# 03_Schematic.net
KiCad netlist of a schematic drawn in Altium Designer
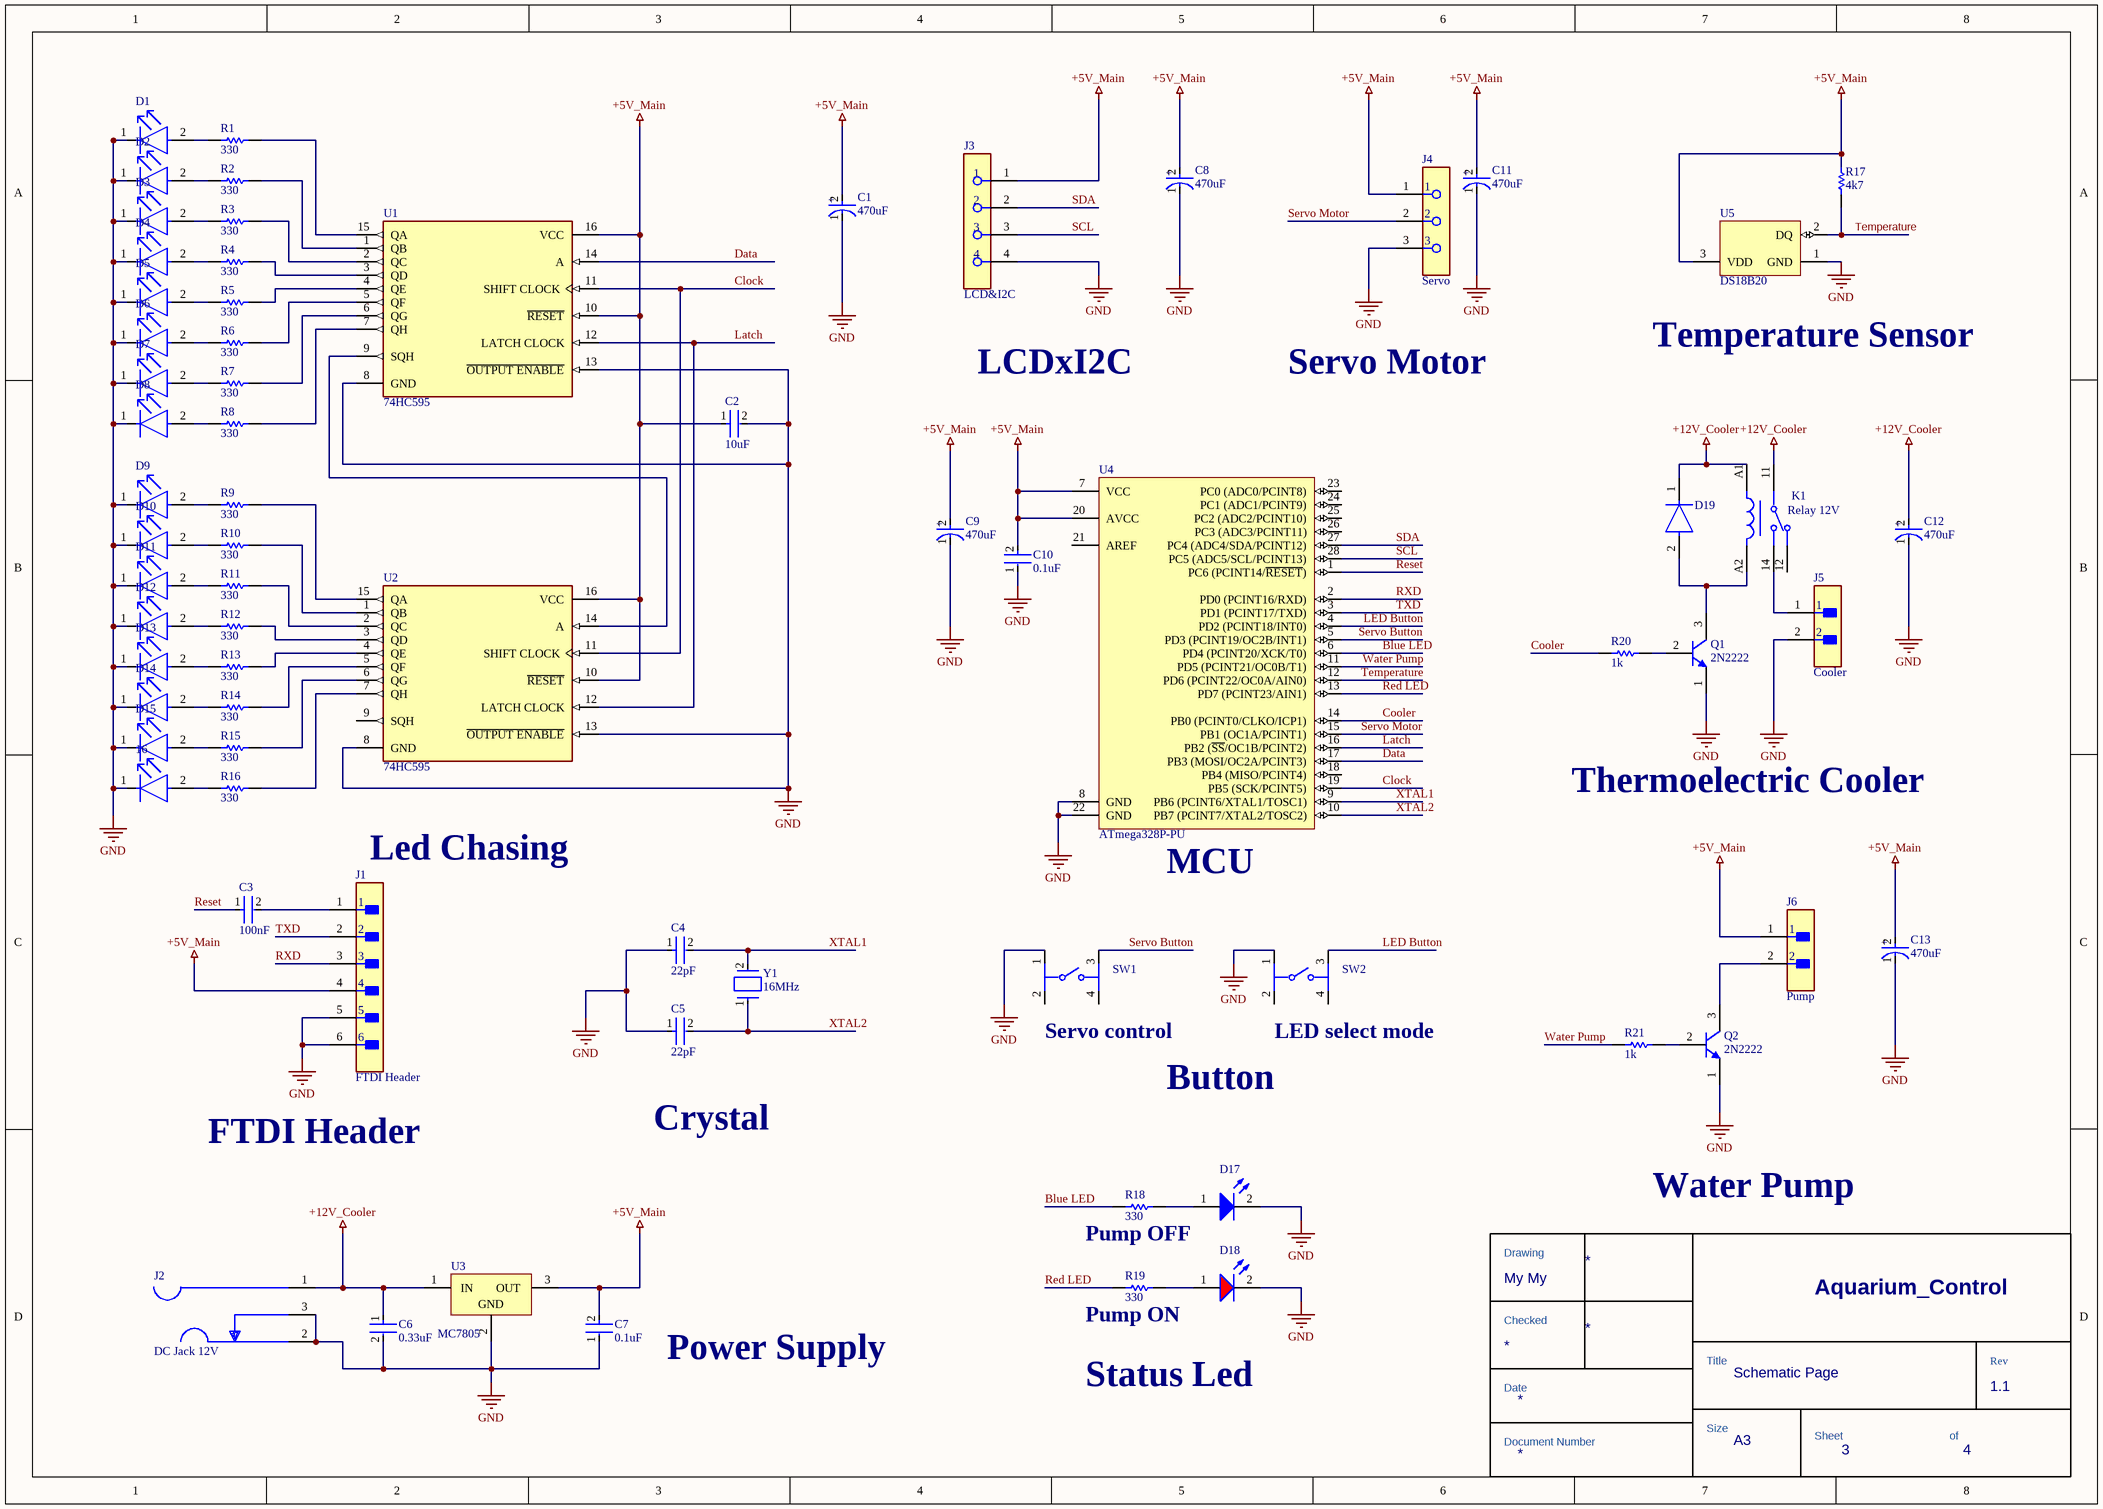
[diagram p0: 03.Schematic.SchDoc]

(export (version "E")
  (design (tool "Eeschema 10.0.6"))
  (components
    (comp (ref "16")
      (value "HLMP-1719")
      (footprint "FP-HLMP-1719-MFG")
      (description "LED YELLOW DIFFUSED T-1 T/H")
      (fields
        (field (name "MANUFACTURER") "Broadcom")
        (field (name "OCTOPART") "https://octopart.com/hlmp-1719-broadcom-71130405")
      )
      (libsource (lib "Altium Content Vault") (part "8706943c75ba83719d021d2fdc84c58"))
    )
    (comp (ref "C1")
      (value "470uF")
      (footprint "FP-FTF-MFG")
      (description "CAP ALUM 470UF 20% 25V SMD")
      (fields (field (name "VOLTAGE") "25V") (field (name "TOLERANCE") "20%"))
      (libsource (lib "Altium Content Vault") (part "a00bbbee19879c290e62620ae7e47b1"))
    )
    (comp (ref "C2")
      (value "10uF")
      (footprint "FP-GRM188-0_1-e0_2_0_55-IPC_A")
      (description "Chip Multilayer Ceramic Capacitors for General Purpose, 0603, 10uF, X5R, 15%, 20%, 6.3V")
      (fields (field (name "VOLTAGE") "6.3V") (field (name "TOLERANCE") "20%"))
      (libsource (lib "Altium Content Vault") (part "02cd4be3c70576c341d710602a673aa"))
    )
    (comp (ref "C3")
      (value "100nF")
      (footprint "FP-CGA3E-0_3-0_1-IPC_A")
      (description "Cap Ceramic 100nF 50V X7R 10% Pad SMD 0603 +125°C Automotive T/R")
      (fields (field (name "TOLERANCE") "10%") (field (name "VOLTAGE") "50V"))
      (libsource (lib "Altium Content Vault") (part "b4654b650e69147ec39a6b967a45e02"))
    )
    (comp (ref "C4")
      (value "22pF")
      (footprint "FP-C0603C-CF-MFG")
      (description "Cap Ceramic 22pF 50V C0G 5% SMD 0603 125°C Paper T/R")
      (fields (field (name "MANUFACTURER PART NUMBER") "C0603C220J5GACTU") (field (name "TOLERANCE") "0.05"))
      (libsource (lib "Altium Content Vault") (part "b4654b650e69147ec39a6b967a45e02"))
    )
    (comp (ref "C5")
      (value "22pF")
      (footprint "FP-C0603C-CF-MFG")
      (description "Cap Ceramic 22pF 50V C0G 5% SMD 0603 125°C Paper T/R")
      (fields (field (name "MANUFACTURER PART NUMBER") "C0603C220J5GACTU") (field (name "TOLERANCE") "0.05"))
      (libsource (lib "Altium Content Vault") (part "b4654b650e69147ec39a6b967a45e02"))
    )
    (comp (ref "C6")
      (value "0.33uF")
      (footprint "FP-C0805C-DN-MFG")
      (description "CAP CER 0.33UF 50V X7R 0805")
      (fields
        (field (name "MANUFACTURER PART NUMBER") "C0805C334K5RACTU")
        (field (name "MANUFACTURER") "KEMET")
      )
      (libsource (lib "Altium Content Vault") (part "b4654b650e69147ec39a6b967a45e02"))
    )
    (comp (ref "C7")
      (value "0.1uF")
      (footprint "FP-GRM15-MFG")
      (description "CAP CER 0.1UF 16V X7R 0402")
      (fields (field (name "MANUFACTURER PART NUMBER") "GRM155R71C104KA88D") (field (name "TOLERANCE") "10%"))
      (libsource (lib "Altium Content Vault") (part "236180d848d6139a670b325ea6854c9"))
    )
    (comp (ref "C8")
      (value "470uF")
      (footprint "FP-FTF-MFG")
      (description "CAP ALUM 470UF 20% 25V SMD")
      (fields (field (name "VOLTAGE") "25V") (field (name "TOLERANCE") "20%"))
      (libsource (lib "Altium Content Vault") (part "a00bbbee19879c290e62620ae7e47b1"))
    )
    (comp (ref "C9")
      (value "470uF")
      (footprint "FP-FTF-MFG")
      (description "CAP ALUM 470UF 20% 25V SMD")
      (fields (field (name "VOLTAGE") "25V") (field (name "TOLERANCE") "20%"))
      (libsource (lib "Altium Content Vault") (part "a00bbbee19879c290e62620ae7e47b1"))
    )
    (comp (ref "C10")
      (value "0.1uF")
      (footprint "FP-GRM15-MFG")
      (description "CAP CER 0.1UF 16V X7R 0402")
      (fields (field (name "MANUFACTURER PART NUMBER") "GRM155R71C104KA88D") (field (name "TOLERANCE") "10%"))
      (libsource (lib "Altium Content Vault") (part "236180d848d6139a670b325ea6854c9"))
    )
    (comp (ref "C11")
      (value "470uF")
      (footprint "FP-FTF-MFG")
      (description "CAP ALUM 470UF 20% 25V SMD")
      (fields (field (name "VOLTAGE") "25V") (field (name "TOLERANCE") "20%"))
      (libsource (lib "Altium Content Vault") (part "a00bbbee19879c290e62620ae7e47b1"))
    )
    (comp (ref "C12")
      (value "470uF")
      (footprint "FP-FTF-MFG")
      (description "CAP ALUM 470UF 20% 25V SMD")
      (fields (field (name "VOLTAGE") "25V") (field (name "TOLERANCE") "20%"))
      (libsource (lib "Altium Content Vault") (part "a00bbbee19879c290e62620ae7e47b1"))
    )
    (comp (ref "C13")
      (value "470uF")
      (footprint "FP-FTF-MFG")
      (description "CAP ALUM 470UF 20% 25V SMD")
      (fields (field (name "VOLTAGE") "25V") (field (name "TOLERANCE") "20%"))
      (libsource (lib "Altium Content Vault") (part "a00bbbee19879c290e62620ae7e47b1"))
    )
    (comp (ref "D1")
      (value "HLMP-1719")
      (footprint "FP-HLMP-1719-MFG")
      (description "LED YELLOW DIFFUSED T-1 T/H")
      (fields
        (field (name "MANUFACTURER") "Broadcom")
        (field (name "OCTOPART") "https://octopart.com/hlmp-1719-broadcom-71130405")
      )
      (libsource (lib "Altium Content Vault") (part "8706943c75ba83719d021d2fdc84c58"))
    )
    (comp (ref "D2")
      (value "HLMP-1719")
      (footprint "FP-HLMP-1719-MFG")
      (description "LED YELLOW DIFFUSED T-1 T/H")
      (fields
        (field (name "MANUFACTURER") "Broadcom")
        (field (name "OCTOPART") "https://octopart.com/hlmp-1719-broadcom-71130405")
      )
      (libsource (lib "Altium Content Vault") (part "8706943c75ba83719d021d2fdc84c58"))
    )
    (comp (ref "D3")
      (value "HLMP-1719")
      (footprint "FP-HLMP-1719-MFG")
      (description "LED YELLOW DIFFUSED T-1 T/H")
      (fields
        (field (name "MANUFACTURER") "Broadcom")
        (field (name "OCTOPART") "https://octopart.com/hlmp-1719-broadcom-71130405")
      )
      (libsource (lib "Altium Content Vault") (part "8706943c75ba83719d021d2fdc84c58"))
    )
    (comp (ref "D4")
      (value "HLMP-1719")
      (footprint "FP-HLMP-1719-MFG")
      (description "LED YELLOW DIFFUSED T-1 T/H")
      (fields
        (field (name "MANUFACTURER") "Broadcom")
        (field (name "OCTOPART") "https://octopart.com/hlmp-1719-broadcom-71130405")
      )
      (libsource (lib "Altium Content Vault") (part "8706943c75ba83719d021d2fdc84c58"))
    )
    (comp (ref "D5")
      (value "HLMP-1719")
      (footprint "FP-HLMP-1719-MFG")
      (description "LED YELLOW DIFFUSED T-1 T/H")
      (fields
        (field (name "MANUFACTURER") "Broadcom")
        (field (name "OCTOPART") "https://octopart.com/hlmp-1719-broadcom-71130405")
      )
      (libsource (lib "Altium Content Vault") (part "8706943c75ba83719d021d2fdc84c58"))
    )
    (comp (ref "D6")
      (value "HLMP-1719")
      (footprint "FP-HLMP-1719-MFG")
      (description "LED YELLOW DIFFUSED T-1 T/H")
      (fields
        (field (name "MANUFACTURER") "Broadcom")
        (field (name "OCTOPART") "https://octopart.com/hlmp-1719-broadcom-71130405")
      )
      (libsource (lib "Altium Content Vault") (part "8706943c75ba83719d021d2fdc84c58"))
    )
    (comp (ref "D7")
      (value "HLMP-1719")
      (footprint "FP-HLMP-1719-MFG")
      (description "LED YELLOW DIFFUSED T-1 T/H")
      (fields
        (field (name "MANUFACTURER") "Broadcom")
        (field (name "OCTOPART") "https://octopart.com/hlmp-1719-broadcom-71130405")
      )
      (libsource (lib "Altium Content Vault") (part "8706943c75ba83719d021d2fdc84c58"))
    )
    (comp (ref "D8")
      (value "HLMP-1719")
      (footprint "FP-HLMP-1719-MFG")
      (description "LED YELLOW DIFFUSED T-1 T/H")
      (fields
        (field (name "MANUFACTURER") "Broadcom")
        (field (name "OCTOPART") "https://octopart.com/hlmp-1719-broadcom-71130405")
      )
      (libsource (lib "Altium Content Vault") (part "8706943c75ba83719d021d2fdc84c58"))
    )
    (comp (ref "D9")
      (value "HLMP-1719")
      (footprint "FP-HLMP-1719-MFG")
      (description "LED YELLOW DIFFUSED T-1 T/H")
      (fields
        (field (name "MANUFACTURER") "Broadcom")
        (field (name "OCTOPART") "https://octopart.com/hlmp-1719-broadcom-71130405")
      )
      (libsource (lib "Altium Content Vault") (part "8706943c75ba83719d021d2fdc84c58"))
    )
    (comp (ref "D10")
      (value "HLMP-1719")
      (footprint "FP-HLMP-1719-MFG")
      (description "LED YELLOW DIFFUSED T-1 T/H")
      (fields
        (field (name "MANUFACTURER") "Broadcom")
        (field (name "OCTOPART") "https://octopart.com/hlmp-1719-broadcom-71130405")
      )
      (libsource (lib "Altium Content Vault") (part "8706943c75ba83719d021d2fdc84c58"))
    )
    (comp (ref "D11")
      (value "HLMP-1719")
      (footprint "FP-HLMP-1719-MFG")
      (description "LED YELLOW DIFFUSED T-1 T/H")
      (fields
        (field (name "MANUFACTURER") "Broadcom")
        (field (name "OCTOPART") "https://octopart.com/hlmp-1719-broadcom-71130405")
      )
      (libsource (lib "Altium Content Vault") (part "8706943c75ba83719d021d2fdc84c58"))
    )
    (comp (ref "D12")
      (value "HLMP-1719")
      (footprint "FP-HLMP-1719-MFG")
      (description "LED YELLOW DIFFUSED T-1 T/H")
      (fields
        (field (name "MANUFACTURER") "Broadcom")
        (field (name "OCTOPART") "https://octopart.com/hlmp-1719-broadcom-71130405")
      )
      (libsource (lib "Altium Content Vault") (part "8706943c75ba83719d021d2fdc84c58"))
    )
    (comp (ref "D13")
      (value "HLMP-1719")
      (footprint "FP-HLMP-1719-MFG")
      (description "LED YELLOW DIFFUSED T-1 T/H")
      (fields
        (field (name "MANUFACTURER") "Broadcom")
        (field (name "OCTOPART") "https://octopart.com/hlmp-1719-broadcom-71130405")
      )
      (libsource (lib "Altium Content Vault") (part "8706943c75ba83719d021d2fdc84c58"))
    )
    (comp (ref "D14")
      (value "HLMP-1719")
      (footprint "FP-HLMP-1719-MFG")
      (description "LED YELLOW DIFFUSED T-1 T/H")
      (fields
        (field (name "MANUFACTURER") "Broadcom")
        (field (name "OCTOPART") "https://octopart.com/hlmp-1719-broadcom-71130405")
      )
      (libsource (lib "Altium Content Vault") (part "8706943c75ba83719d021d2fdc84c58"))
    )
    (comp (ref "D15")
      (value "HLMP-1719")
      (footprint "FP-HLMP-1719-MFG")
      (description "LED YELLOW DIFFUSED T-1 T/H")
      (fields
        (field (name "MANUFACTURER") "Broadcom")
        (field (name "OCTOPART") "https://octopart.com/hlmp-1719-broadcom-71130405")
      )
      (libsource (lib "Altium Content Vault") (part "8706943c75ba83719d021d2fdc84c58"))
    )
    (comp (ref "D17")
      (value "151051BS04000")
      (footprint "WL-TMRC_D5.9H8.7")
      (libsource (lib "Altium Content Vault") (part "LED_Blue_1A-2K"))
    )
    (comp (ref "D18")
      (value "151031SS04000")
      (footprint "WL-TMRC_D3.95H5.3")
      (libsource (lib "Altium Content Vault") (part "LED_Red_1A-2K"))
    )
    (comp (ref "D19")
      (value "1N4148")
      (footprint "FP-017AG-MFG")
      (description "DIODE GEN PURP 100V 200MA DO35")
      (fields (field (name "VOLTAGE") "100V"))
      (libsource (lib "Altium Content Vault") (part "d7152d700b627762746794eb795d46e"))
    )
    (comp (ref "J1")
      (value "FTDI Header")
      (footprint "FP-GBC06SBSN-M89-MFG")
      (description "CONN HEADER SMD R/A 6POS 2.54MM")
      (libsource (lib "Altium Content Vault") (part "f2cb566baf1c37ab5a3b8e90bbeafd6"))
    )
    (comp (ref "J2")
      (value "DC Jack 12V")
      (footprint "FP-L722RA-MFG")
      (description "CONN POWER JACK 2.1MM ID SOLDER")
      (fields
        (field (name "MANUFACTURER") "Switchcraft")
        (field (name "OCTOPART") "https://octopart.com/l722ra-switchcraft-28281")
      )
      (libsource (lib "Altium Content Vault") (part "a3a9313a7a4e897c84d876205db69ad"))
    )
    (comp (ref "J3")
      (value "LCD&I2C")
      (footprint "FP-LPPB041NFFN-RC-MFG")
      (description "CONN HDR 4POS 0.05 GOLD PCB")
      (libsource (lib "Altium Content Vault") (part "56792406a6bd5c25e158f553ecd1aa7"))
    )
    (comp (ref "J4")
      (value "Servo")
      (footprint "FP-PPTC031LGBN-RC-MFG")
      (libsource (lib "Altium Content Vault") (part "9e3c5d0b45d2cf0495be8a0529c1856"))
    )
    (comp (ref "J5")
      (value "Cooler")
      (footprint "FP-PEC02SABN-MFG")
      (description "CONN HEADER VERT 2POS 2.54MM")
      (libsource (lib "Altium Content Vault") (part "3bc925449376181038e59eaffc5286c"))
    )
    (comp (ref "J6")
      (value "Pump")
      (footprint "FP-PEC02SABN-MFG")
      (description "CONN HEADER VERT 2POS 2.54MM")
      (libsource (lib "Altium Content Vault") (part "3bc925449376181038e59eaffc5286c"))
    )
    (comp (ref "K1")
      (value "RTB14005")
      (footprint "FP-RTB14005-MFG")
      (description "RELAY GEN PURPOSE SPDT 12A 5V")
      (libsource (lib "Altium Content Vault") (part "073c63e877000fb1b84f95b80705c0f"))
    )
    (comp (ref "Q1")
      (value "2N2222")
      (footprint "MLTC-TO-18-3")
      (description "Low Power Bipolar NPN Transistor, 30 V, -65 to 200 degC, 3-Pin TO-18, RoHS, Bulk")
      (fields (field (name "MANUFACTURER") "Multicomp"))
      (libsource (lib "Altium Content Vault") (part "BJT-NPN-EBC-3"))
    )
    (comp (ref "Q2")
      (value "2N2222")
      (footprint "MLTC-TO-18-3")
      (description "Low Power Bipolar NPN Transistor, 30 V, -65 to 200 degC, 3-Pin TO-18, RoHS, Bulk")
      (fields (field (name "MANUFACTURER") "Multicomp"))
      (libsource (lib "Altium Content Vault") (part "BJT-NPN-EBC-3"))
    )
    (comp (ref "R1")
      (value "330")
      (footprint "RESC1608X55X30LL15T15")
      (description "Chip Resistor, 330 Ohm, +/- 1%, 0.1 W, -55 to 155 degC, 0603 (1608 Metric), RoHS, Tape and Reel")
      (libsource (lib "Altium Content Vault") (part "RES-2"))
    )
    (comp (ref "R2")
      (value "330")
      (footprint "RESC1608X55X30LL15T15")
      (description "Chip Resistor, 330 Ohm, +/- 1%, 0.1 W, -55 to 155 degC, 0603 (1608 Metric), RoHS, Tape and Reel")
      (libsource (lib "Altium Content Vault") (part "RES-2"))
    )
    (comp (ref "R3")
      (value "330")
      (footprint "RESC1608X55X30LL15T15")
      (description "Chip Resistor, 330 Ohm, +/- 1%, 0.1 W, -55 to 155 degC, 0603 (1608 Metric), RoHS, Tape and Reel")
      (libsource (lib "Altium Content Vault") (part "RES-2"))
    )
    (comp (ref "R4")
      (value "330")
      (footprint "RESC1608X55X30LL15T15")
      (description "Chip Resistor, 330 Ohm, +/- 1%, 0.1 W, -55 to 155 degC, 0603 (1608 Metric), RoHS, Tape and Reel")
      (libsource (lib "Altium Content Vault") (part "RES-2"))
    )
    (comp (ref "R5")
      (value "330")
      (footprint "RESC1608X55X30LL15T15")
      (description "Chip Resistor, 330 Ohm, +/- 1%, 0.1 W, -55 to 155 degC, 0603 (1608 Metric), RoHS, Tape and Reel")
      (libsource (lib "Altium Content Vault") (part "RES-2"))
    )
    (comp (ref "R6")
      (value "330")
      (footprint "RESC1608X55X30LL15T15")
      (description "Chip Resistor, 330 Ohm, +/- 1%, 0.1 W, -55 to 155 degC, 0603 (1608 Metric), RoHS, Tape and Reel")
      (libsource (lib "Altium Content Vault") (part "RES-2"))
    )
    (comp (ref "R7")
      (value "330")
      (footprint "RESC1608X55X30LL15T15")
      (description "Chip Resistor, 330 Ohm, +/- 1%, 0.1 W, -55 to 155 degC, 0603 (1608 Metric), RoHS, Tape and Reel")
      (libsource (lib "Altium Content Vault") (part "RES-2"))
    )
    (comp (ref "R8")
      (value "330")
      (footprint "RESC1608X55X30LL15T15")
      (description "Chip Resistor, 330 Ohm, +/- 1%, 0.1 W, -55 to 155 degC, 0603 (1608 Metric), RoHS, Tape and Reel")
      (libsource (lib "Altium Content Vault") (part "RES-2"))
    )
    (comp (ref "R9")
      (value "330")
      (footprint "RESC1608X55X30LL15T15")
      (description "Chip Resistor, 330 Ohm, +/- 1%, 0.1 W, -55 to 155 degC, 0603 (1608 Metric), RoHS, Tape and Reel")
      (libsource (lib "Altium Content Vault") (part "RES-2"))
    )
    (comp (ref "R10")
      (value "330")
      (footprint "RESC1608X55X30LL15T15")
      (description "Chip Resistor, 330 Ohm, +/- 1%, 0.1 W, -55 to 155 degC, 0603 (1608 Metric), RoHS, Tape and Reel")
      (libsource (lib "Altium Content Vault") (part "RES-2"))
    )
    (comp (ref "R11")
      (value "330")
      (footprint "RESC1608X55X30LL15T15")
      (description "Chip Resistor, 330 Ohm, +/- 1%, 0.1 W, -55 to 155 degC, 0603 (1608 Metric), RoHS, Tape and Reel")
      (libsource (lib "Altium Content Vault") (part "RES-2"))
    )
    (comp (ref "R12")
      (value "330")
      (footprint "RESC1608X55X30LL15T15")
      (description "Chip Resistor, 330 Ohm, +/- 1%, 0.1 W, -55 to 155 degC, 0603 (1608 Metric), RoHS, Tape and Reel")
      (libsource (lib "Altium Content Vault") (part "RES-2"))
    )
    (comp (ref "R13")
      (value "330")
      (footprint "RESC1608X55X30LL15T15")
      (description "Chip Resistor, 330 Ohm, +/- 1%, 0.1 W, -55 to 155 degC, 0603 (1608 Metric), RoHS, Tape and Reel")
      (libsource (lib "Altium Content Vault") (part "RES-2"))
    )
    (comp (ref "R14")
      (value "330")
      (footprint "RESC1608X55X30LL15T15")
      (description "Chip Resistor, 330 Ohm, +/- 1%, 0.1 W, -55 to 155 degC, 0603 (1608 Metric), RoHS, Tape and Reel")
      (libsource (lib "Altium Content Vault") (part "RES-2"))
    )
    (comp (ref "R15")
      (value "330")
      (footprint "RESC1608X55X30LL15T15")
      (description "Chip Resistor, 330 Ohm, +/- 1%, 0.1 W, -55 to 155 degC, 0603 (1608 Metric), RoHS, Tape and Reel")
      (libsource (lib "Altium Content Vault") (part "RES-2"))
    )
    (comp (ref "R16")
      (value "330")
      (footprint "RESC1608X55X30LL15T15")
      (description "Chip Resistor, 330 Ohm, +/- 1%, 0.1 W, -55 to 155 degC, 0603 (1608 Metric), RoHS, Tape and Reel")
      (libsource (lib "Altium Content Vault") (part "RES-2"))
    )
    (comp (ref "R17")
      (value "4k7")
      (footprint "RESC1608X55X30LL15T15")
      (description "Chip Resistor, 330 Ohm, +/- 1%, 0.1 W, -55 to 155 degC, 0603 (1608 Metric), RoHS, Tape and Reel")
      (libsource (lib "Altium Content Vault") (part "RES-2"))
    )
    (comp (ref "R18")
      (value "330")
      (footprint "RESC1608X55X30LL15T15")
      (description "Chip Resistor, 330 Ohm, +/- 1%, 0.1 W, -55 to 155 degC, 0603 (1608 Metric), RoHS, Tape and Reel")
      (libsource (lib "Altium Content Vault") (part "RES-2"))
    )
    (comp (ref "R19")
      (value "330")
      (footprint "RESC1608X55X30LL15T15")
      (description "Chip Resistor, 330 Ohm, +/- 1%, 0.1 W, -55 to 155 degC, 0603 (1608 Metric), RoHS, Tape and Reel")
      (libsource (lib "Altium Content Vault") (part "RES-2"))
    )
    (comp (ref "R20")
      (value "1k")
      (footprint "RESC2013X60X35ML10T20")
      (description "Chip Resistor, 1 KOhm, +/- 1%, 125 mW, -55 to 155 degC, 0805 (2012 Metric), RoHS, Tape and Reel")
      (fields (field (name "TOLERANCE") "1%") (field (name "MANUFACTURER") "Yageo"))
      (libsource (lib "Altium Content Vault") (part "RES-2"))
    )
    (comp (ref "R21")
      (value "1k")
      (footprint "RESC2013X60X35ML10T20")
      (description "Chip Resistor, 1 KOhm, +/- 1%, 125 mW, -55 to 155 degC, 0805 (2012 Metric), RoHS, Tape and Reel")
      (fields (field (name "TOLERANCE") "1%") (field (name "MANUFACTURER") "Yageo"))
      (libsource (lib "Altium Content Vault") (part "RES-2"))
    )
    (comp (ref "SW1")
      (value "1-1825910-5")
      (footprint "FP-1-1825910-5-MFG")
      (description "SWITCH TACTILE SPST-NO 0.05A 24V")
      (libsource (lib "Altium Content Vault") (part "b8895f3f4cefb76e1819d2863dba89b"))
    )
    (comp (ref "SW2")
      (value "1-1825910-5")
      (footprint "FP-1-1825910-5-MFG")
      (description "SWITCH TACTILE SPST-NO 0.05A 24V")
      (libsource (lib "Altium Content Vault") (part "b8895f3f4cefb76e1819d2863dba89b"))
    )
    (comp (ref "U1")
      (value "74HC595")
      (footprint "FP-751B-05-MFG")
      (description "IC SHIFT REGISTR 8BIT 3ST 16SOIC")
      (fields
        (field (name "MANUFACTURER PART NUMBER") "MC74HC595ADR2G")
        (field (name "MANUFACTURER") "On Semiconductor")
      )
      (libsource (lib "Altium Content Vault") (part "27cf43c180b12d231d6324aa18dda51"))
    )
    (comp (ref "U2")
      (value "74HC595")
      (footprint "FP-751B-05-MFG")
      (description "IC SHIFT REGISTR 8BIT 3ST 16SOIC")
      (fields
        (field (name "MANUFACTURER PART NUMBER") "MC74HC595ADR2G")
        (field (name "MANUFACTURER") "On Semiconductor")
      )
      (libsource (lib "Altium Content Vault") (part "27cf43c180b12d231d6324aa18dda51"))
    )
    (comp (ref "U3")
      (value "MC7805")
      (footprint "ONSC-TO-220-3-221AB-01")
      (description "Positive Voltage Regulator, 1 A, 5 V, 0 to 125 degC, 3-Pin TO-220, RoHS, Tube")
      (fields (field (name "MANUFACTURER") "ON Semiconductor"))
      (libsource (lib "Altium Content Vault") (part "ONSC-MC7805CTG-TO-220-3"))
    )
    (comp (ref "U4")
      (value "ATmega328P-PU")
      (footprint "28P3")
      (libsource (lib "Altium Content Vault") (part "MC-8B-ATM48-IL28"))
    )
    (comp (ref "U5")
      (value "DS18B20")
      (footprint "Q3+1")
      (libsource (lib "Altium Content Vault") (part "SEN-TEMP-DS1821-SIL3"))
    )
    (comp (ref "Y1")
      (value "16MHz")
      (footprint "FP-XRCHA-MFG")
      (description "CRYSTAL 16.0000MHZ 8PF SMD")
      (fields (field (name "TOLERANCE") "100ppm"))
      (libsource (lib "Altium Content Vault") (part "c23a69dc6c9e2f18f2079038eb95dd1"))
    )
  )
  (nets
    (net (code "1") (name "+5V_Main") (class "Default")
      (node (ref "C1") (pin "2") (pinfunction "A_2") (pintype "passive"))
      (node (ref "C10") (pin "2") (pinfunction "2_2") (pintype "passive"))
      (node (ref "C11") (pin "2") (pinfunction "A_2") (pintype "passive"))
      (node (ref "C13") (pin "2") (pinfunction "A_2") (pintype "passive"))
      (node (ref "C2") (pin "1") (pinfunction "1_1") (pintype "passive"))
      (node (ref "C7") (pin "2") (pinfunction "2_2") (pintype "passive"))
      (node (ref "C8") (pin "2") (pinfunction "A_2") (pintype "passive"))
      (node (ref "C9") (pin "2") (pinfunction "A_2") (pintype "passive"))
      (node (ref "J1") (pin "4") (pinfunction "4_4") (pintype "passive"))
      (node (ref "J3") (pin "1") (pinfunction "1_1") (pintype "passive"))
      (node (ref "J4") (pin "1") (pinfunction "1_1") (pintype "passive"))
      (node (ref "J6") (pin "1") (pinfunction "1_1") (pintype "passive"))
      (node (ref "R17") (pin "2") (pinfunction "2_2") (pintype "passive"))
      (node (ref "U1") (pin "10") (pinfunction "~{RESET}_10") (pintype "input"))
      (node (ref "U1") (pin "16") (pinfunction "VCC_16") (pintype "power_in"))
      (node (ref "U2") (pin "10") (pinfunction "~{RESET}_10") (pintype "input"))
      (node (ref "U2") (pin "16") (pinfunction "VCC_16") (pintype "power_in"))
      (node (ref "U3") (pin "3") (pinfunction "OUT_3") (pintype "power_in"))
      (node (ref "U4") (pin "20") (pinfunction "AVCC_20") (pintype "power_in"))
      (node (ref "U4") (pin "7") (pinfunction "VCC_7") (pintype "power_in"))
      (node (ref "U5") (pin "3") (pinfunction "VDD_3") (pintype "power_in"))
    )
    (net (code "2") (name "+12V_Cooler") (class "Default")
      (node (ref "C12") (pin "2") (pinfunction "A_2") (pintype "passive"))
      (node (ref "C6") (pin "1") (pinfunction "1_1") (pintype "passive"))
      (node (ref "D19") (pin "1") (pinfunction "C_1") (pintype "passive"))
      (node (ref "J2") (pin "1") (pinfunction "CENTER_PIN_1") (pintype "passive"))
      (node (ref "K1") (pin "11") (pinfunction "11_11") (pintype "passive"))
      (node (ref "K1") (pin "A1") (pinfunction "A1_A1") (pintype "passive"))
      (node (ref "U3") (pin "1") (pinfunction "IN_1") (pintype "power_in"))
    )
    (net (code "3") (name "/Blue LED") (class "Default")
      (node (ref "R18") (pin "1") (pinfunction "1_1") (pintype "passive"))
      (node (ref "U4") (pin "6") (pinfunction "PD4_(PCINT20/XCK/T0)_6") (pintype "bidirectional"))
    )
    (net (code "4") (name "/Clock") (class "Default")
      (node (ref "U1") (pin "11") (pinfunction "SHIFT_CLOCK_11") (pintype "input"))
      (node (ref "U2") (pin "11") (pinfunction "SHIFT_CLOCK_11") (pintype "input"))
      (node (ref "U4") (pin "19") (pinfunction "PB5_(SCK/PCINT5)_19") (pintype "bidirectional"))
    )
    (net (code "5") (name "/Cooler") (class "Default")
      (node (ref "R20") (pin "1") (pinfunction "1_1") (pintype "passive"))
      (node (ref "U4") (pin "14") (pinfunction "PB0_(PCINT0/CLKO/ICP1)_14") (pintype "bidirectional"))
    )
    (net (code "6") (name "/Data") (class "Default")
      (node (ref "U1") (pin "14") (pinfunction "A_14") (pintype "input"))
      (node (ref "U4") (pin "17") (pinfunction "PB3_(MOSI/OC2A/PCINT3)_17") (pintype "bidirectional"))
    )
    (net (code "7") (name "/LED Button") (class "Default")
      (node (ref "SW2") (pin "3") (pinfunction "3_3") (pintype "passive"))
      (node (ref "U4") (pin "4") (pinfunction "PD2_(PCINT18/INT0)_4") (pintype "bidirectional"))
    )
    (net (code "8") (name "/Latch") (class "Default")
      (node (ref "U1") (pin "12") (pinfunction "LATCH_CLOCK_12") (pintype "input"))
      (node (ref "U2") (pin "12") (pinfunction "LATCH_CLOCK_12") (pintype "input"))
      (node (ref "U4") (pin "16") (pinfunction "PB2_(~{SS}/OC1B/PCINT2)_16") (pintype "bidirectional"))
    )
    (net (code "9") (name "/RXD") (class "Default")
      (node (ref "J1") (pin "3") (pinfunction "3_3") (pintype "passive"))
      (node (ref "U4") (pin "2") (pinfunction "PD0_(PCINT16/RXD)_2") (pintype "bidirectional"))
    )
    (net (code "10") (name "/Red LED") (class "Default")
      (node (ref "R19") (pin "1") (pinfunction "1_1") (pintype "passive"))
      (node (ref "U4") (pin "13") (pinfunction "PD7_(PCINT23/AIN1)_13") (pintype "bidirectional"))
    )
    (net (code "11") (name "/Reset") (class "Default")
      (node (ref "C3") (pin "1") (pinfunction "1_1") (pintype "passive"))
      (node (ref "U4") (pin "1") (pinfunction "PC6_(PCINT14/~{RESET})_1") (pintype "bidirectional"))
    )
    (net (code "12") (name "/SCL") (class "Default")
      (node (ref "J3") (pin "3") (pinfunction "3_3") (pintype "passive"))
      (node (ref "U4") (pin "28") (pinfunction "PC5_(ADC5/SCL/PCINT13)_28") (pintype "bidirectional"))
    )
    (net (code "13") (name "/SDA") (class "Default")
      (node (ref "J3") (pin "2") (pinfunction "2_2") (pintype "passive"))
      (node (ref "U4") (pin "27") (pinfunction "PC4_(ADC4/SDA/PCINT12)_27") (pintype "bidirectional"))
    )
    (net (code "14") (name "/Servo Button") (class "Default")
      (node (ref "SW1") (pin "3") (pinfunction "3_3") (pintype "passive"))
      (node (ref "U4") (pin "5") (pinfunction "PD3_(PCINT19/OC2B/INT1)_5") (pintype "bidirectional"))
    )
    (net (code "15") (name "/Servo Motor") (class "Default")
      (node (ref "J4") (pin "2") (pinfunction "2_2") (pintype "passive"))
      (node (ref "U4") (pin "15") (pinfunction "PB1_(OC1A/PCINT1)_15") (pintype "bidirectional"))
    )
    (net (code "16") (name "/TXD") (class "Default")
      (node (ref "J1") (pin "2") (pinfunction "2_2") (pintype "passive"))
      (node (ref "U4") (pin "3") (pinfunction "PD1_(PCINT17/TXD)_3") (pintype "bidirectional"))
    )
    (net (code "17") (name "/Temperature") (class "Default")
      (node (ref "R17") (pin "1") (pinfunction "1_1") (pintype "passive"))
      (node (ref "U4") (pin "12") (pinfunction "PD6_(PCINT22/OC0A/AIN0)_12") (pintype "bidirectional"))
      (node (ref "U5") (pin "2") (pinfunction "DQ_2") (pintype "bidirectional"))
    )
    (net (code "18") (name "/Water Pump") (class "Default")
      (node (ref "R21") (pin "1") (pinfunction "1_1") (pintype "passive"))
      (node (ref "U4") (pin "11") (pinfunction "PD5_(PCINT21/OC0B/T1)_11") (pintype "bidirectional"))
    )
    (net (code "19") (name "/XTAL1") (class "Default")
      (node (ref "C4") (pin "2") (pinfunction "2_2") (pintype "passive"))
      (node (ref "U4") (pin "9") (pinfunction "PB6_(PCINT6/XTAL1/TOSC1)_9") (pintype "bidirectional"))
      (node (ref "Y1") (pin "2") (pinfunction "2_2") (pintype "passive"))
    )
    (net (code "20") (name "/XTAL2") (class "Default")
      (node (ref "C5") (pin "2") (pinfunction "2_2") (pintype "passive"))
      (node (ref "U4") (pin "10") (pinfunction "PB7_(PCINT7/XTAL2/TOSC2)_10") (pintype "bidirectional"))
      (node (ref "Y1") (pin "1") (pinfunction "1_1") (pintype "passive"))
    )
    (net (code "21") (name "GND") (class "Default")
      (node (ref "16") (pin "1") (pinfunction "C_1") (pintype "passive"))
      (node (ref "C1") (pin "1") (pinfunction "C_1") (pintype "passive"))
      (node (ref "C10") (pin "1") (pinfunction "1_1") (pintype "passive"))
      (node (ref "C11") (pin "1") (pinfunction "C_1") (pintype "passive"))
      (node (ref "C12") (pin "1") (pinfunction "C_1") (pintype "passive"))
      (node (ref "C13") (pin "1") (pinfunction "C_1") (pintype "passive"))
      (node (ref "C2") (pin "2") (pinfunction "2_2") (pintype "passive"))
      (node (ref "C4") (pin "1") (pinfunction "1_1") (pintype "passive"))
      (node (ref "C5") (pin "1") (pinfunction "1_1") (pintype "passive"))
      (node (ref "C6") (pin "2") (pinfunction "2_2") (pintype "passive"))
      (node (ref "C7") (pin "1") (pinfunction "1_1") (pintype "passive"))
      (node (ref "C8") (pin "1") (pinfunction "C_1") (pintype "passive"))
      (node (ref "C9") (pin "1") (pinfunction "C_1") (pintype "passive"))
      (node (ref "D1") (pin "1") (pinfunction "C_1") (pintype "passive"))
      (node (ref "D10") (pin "1") (pinfunction "C_1") (pintype "passive"))
      (node (ref "D11") (pin "1") (pinfunction "C_1") (pintype "passive"))
      (node (ref "D12") (pin "1") (pinfunction "C_1") (pintype "passive"))
      (node (ref "D13") (pin "1") (pinfunction "C_1") (pintype "passive"))
      (node (ref "D14") (pin "1") (pinfunction "C_1") (pintype "passive"))
      (node (ref "D15") (pin "1") (pinfunction "C_1") (pintype "passive"))
      (node (ref "D17") (pin "2") (pinfunction "K_2") (pintype "passive"))
      (node (ref "D18") (pin "2") (pinfunction "K_2") (pintype "passive"))
      (node (ref "D2") (pin "1") (pinfunction "C_1") (pintype "passive"))
      (node (ref "D3") (pin "1") (pinfunction "C_1") (pintype "passive"))
      (node (ref "D4") (pin "1") (pinfunction "C_1") (pintype "passive"))
      (node (ref "D5") (pin "1") (pinfunction "C_1") (pintype "passive"))
      (node (ref "D6") (pin "1") (pinfunction "C_1") (pintype "passive"))
      (node (ref "D7") (pin "1") (pinfunction "C_1") (pintype "passive"))
      (node (ref "D8") (pin "1") (pinfunction "C_1") (pintype "passive"))
      (node (ref "D9") (pin "1") (pinfunction "C_1") (pintype "passive"))
      (node (ref "J1") (pin "5") (pinfunction "5_5") (pintype "passive"))
      (node (ref "J1") (pin "6") (pinfunction "6_6") (pintype "passive"))
      (node (ref "J2") (pin "2") (pinfunction "SLEEVE_2") (pintype "passive"))
      (node (ref "J2") (pin "3") (pinfunction "SLEEVE_SHUNT_3") (pintype "passive"))
      (node (ref "J3") (pin "4") (pinfunction "4_4") (pintype "passive"))
      (node (ref "J4") (pin "3") (pinfunction "3_3") (pintype "passive"))
      (node (ref "J5") (pin "2") (pinfunction "2_2") (pintype "passive"))
      (node (ref "Q1") (pin "1") (pinfunction "E_1") (pintype "passive"))
      (node (ref "Q2") (pin "1") (pinfunction "E_1") (pintype "passive"))
      (node (ref "SW1") (pin "1") (pinfunction "1_1") (pintype "passive"))
      (node (ref "SW2") (pin "1") (pinfunction "1_1") (pintype "passive"))
      (node (ref "U1") (pin "13") (pinfunction "~{OUTPUT_ENABLE}_13") (pintype "input"))
      (node (ref "U1") (pin "8") (pinfunction "GND_8") (pintype "power_in"))
      (node (ref "U2") (pin "13") (pinfunction "~{OUTPUT_ENABLE}_13") (pintype "input"))
      (node (ref "U2") (pin "8") (pinfunction "GND_8") (pintype "power_in"))
      (node (ref "U3") (pin "2") (pinfunction "GND_2") (pintype "power_in"))
      (node (ref "U4") (pin "22") (pinfunction "GND_22") (pintype "power_in"))
      (node (ref "U4") (pin "8") (pinfunction "GND_8") (pintype "power_in"))
      (node (ref "U5") (pin "1") (pinfunction "GND_1") (pintype "power_in"))
    )
    (net (code "22") (name "Net-(16-A)") (class "Default")
      (node (ref "16") (pin "2") (pinfunction "A_2") (pintype "passive"))
      (node (ref "R16") (pin "1") (pinfunction "1_1") (pintype "passive"))
    )
    (net (code "23") (name "Net-(C3-Pad2)") (class "Default")
      (node (ref "C3") (pin "2") (pinfunction "2_2") (pintype "passive"))
      (node (ref "J1") (pin "1") (pinfunction "1_1") (pintype "passive"))
    )
    (net (code "24") (name "Net-(D1-A)") (class "Default")
      (node (ref "D1") (pin "2") (pinfunction "A_2") (pintype "passive"))
      (node (ref "R1") (pin "1") (pinfunction "1_1") (pintype "passive"))
    )
    (net (code "25") (name "Net-(D2-A)") (class "Default")
      (node (ref "D2") (pin "2") (pinfunction "A_2") (pintype "passive"))
      (node (ref "R2") (pin "1") (pinfunction "1_1") (pintype "passive"))
    )
    (net (code "26") (name "Net-(D3-A)") (class "Default")
      (node (ref "D3") (pin "2") (pinfunction "A_2") (pintype "passive"))
      (node (ref "R3") (pin "1") (pinfunction "1_1") (pintype "passive"))
    )
    (net (code "27") (name "Net-(D4-A)") (class "Default")
      (node (ref "D4") (pin "2") (pinfunction "A_2") (pintype "passive"))
      (node (ref "R4") (pin "1") (pinfunction "1_1") (pintype "passive"))
    )
    (net (code "28") (name "Net-(D5-A)") (class "Default")
      (node (ref "D5") (pin "2") (pinfunction "A_2") (pintype "passive"))
      (node (ref "R5") (pin "1") (pinfunction "1_1") (pintype "passive"))
    )
    (net (code "29") (name "Net-(D6-A)") (class "Default")
      (node (ref "D6") (pin "2") (pinfunction "A_2") (pintype "passive"))
      (node (ref "R6") (pin "1") (pinfunction "1_1") (pintype "passive"))
    )
    (net (code "30") (name "Net-(D7-A)") (class "Default")
      (node (ref "D7") (pin "2") (pinfunction "A_2") (pintype "passive"))
      (node (ref "R7") (pin "1") (pinfunction "1_1") (pintype "passive"))
    )
    (net (code "31") (name "Net-(D8-A)") (class "Default")
      (node (ref "D8") (pin "2") (pinfunction "A_2") (pintype "passive"))
      (node (ref "R8") (pin "1") (pinfunction "1_1") (pintype "passive"))
    )
    (net (code "32") (name "Net-(D9-A)") (class "Default")
      (node (ref "D9") (pin "2") (pinfunction "A_2") (pintype "passive"))
      (node (ref "R9") (pin "1") (pinfunction "1_1") (pintype "passive"))
    )
    (net (code "33") (name "Net-(D10-A)") (class "Default")
      (node (ref "D10") (pin "2") (pinfunction "A_2") (pintype "passive"))
      (node (ref "R10") (pin "1") (pinfunction "1_1") (pintype "passive"))
    )
    (net (code "34") (name "Net-(D11-A)") (class "Default")
      (node (ref "D11") (pin "2") (pinfunction "A_2") (pintype "passive"))
      (node (ref "R11") (pin "1") (pinfunction "1_1") (pintype "passive"))
    )
    (net (code "35") (name "Net-(D12-A)") (class "Default")
      (node (ref "D12") (pin "2") (pinfunction "A_2") (pintype "passive"))
      (node (ref "R12") (pin "1") (pinfunction "1_1") (pintype "passive"))
    )
    (net (code "36") (name "Net-(D13-A)") (class "Default")
      (node (ref "D13") (pin "2") (pinfunction "A_2") (pintype "passive"))
      (node (ref "R13") (pin "1") (pinfunction "1_1") (pintype "passive"))
    )
    (net (code "37") (name "Net-(D14-A)") (class "Default")
      (node (ref "D14") (pin "2") (pinfunction "A_2") (pintype "passive"))
      (node (ref "R14") (pin "1") (pinfunction "1_1") (pintype "passive"))
    )
    (net (code "38") (name "Net-(D15-A)") (class "Default")
      (node (ref "D15") (pin "2") (pinfunction "A_2") (pintype "passive"))
      (node (ref "R15") (pin "1") (pinfunction "1_1") (pintype "passive"))
    )
    (net (code "39") (name "Net-(D17-A)") (class "Default")
      (node (ref "D17") (pin "1") (pinfunction "A_1") (pintype "passive"))
      (node (ref "R18") (pin "2") (pinfunction "2_2") (pintype "passive"))
    )
    (net (code "40") (name "Net-(D18-A)") (class "Default")
      (node (ref "D18") (pin "1") (pinfunction "A_1") (pintype "passive"))
      (node (ref "R19") (pin "2") (pinfunction "2_2") (pintype "passive"))
    )
    (net (code "41") (name "Net-(D19-A)") (class "Default")
      (node (ref "D19") (pin "2") (pinfunction "A_2") (pintype "passive"))
      (node (ref "K1") (pin "A2") (pinfunction "A2_A2") (pintype "passive"))
      (node (ref "Q1") (pin "3") (pinfunction "C_3") (pintype "passive"))
    )
    (net (code "42") (name "Net-(J5-Pad1)") (class "Default")
      (node (ref "J5") (pin "1") (pinfunction "1_1") (pintype "passive"))
      (node (ref "K1") (pin "14") (pinfunction "14_14") (pintype "passive"))
    )
    (net (code "43") (name "Net-(Q1-B)") (class "Default")
      (node (ref "Q1") (pin "2") (pinfunction "B_2") (pintype "passive"))
      (node (ref "R20") (pin "2") (pinfunction "2_2") (pintype "passive"))
    )
    (net (code "44") (name "Net-(Q2-B)") (class "Default")
      (node (ref "Q2") (pin "2") (pinfunction "B_2") (pintype "passive"))
      (node (ref "R21") (pin "2") (pinfunction "2_2") (pintype "passive"))
    )
    (net (code "45") (name "Net-(Q2-C)") (class "Default")
      (node (ref "J6") (pin "2") (pinfunction "2_2") (pintype "passive"))
      (node (ref "Q2") (pin "3") (pinfunction "C_3") (pintype "passive"))
    )
    (net (code "46") (name "Net-(U1-QA)") (class "Default")
      (node (ref "R1") (pin "2") (pinfunction "2_2") (pintype "passive"))
      (node (ref "U1") (pin "15") (pinfunction "QA_15") (pintype "output"))
    )
    (net (code "47") (name "Net-(U1-QB)") (class "Default")
      (node (ref "R2") (pin "2") (pinfunction "2_2") (pintype "passive"))
      (node (ref "U1") (pin "1") (pinfunction "QB_1") (pintype "output"))
    )
    (net (code "48") (name "Net-(U1-QC)") (class "Default")
      (node (ref "R3") (pin "2") (pinfunction "2_2") (pintype "passive"))
      (node (ref "U1") (pin "2") (pinfunction "QC_2") (pintype "output"))
    )
    (net (code "49") (name "Net-(U1-QD)") (class "Default")
      (node (ref "R4") (pin "2") (pinfunction "2_2") (pintype "passive"))
      (node (ref "U1") (pin "3") (pinfunction "QD_3") (pintype "output"))
    )
    (net (code "50") (name "Net-(U1-QE)") (class "Default")
      (node (ref "R5") (pin "2") (pinfunction "2_2") (pintype "passive"))
      (node (ref "U1") (pin "4") (pinfunction "QE_4") (pintype "output"))
    )
    (net (code "51") (name "Net-(U1-QF)") (class "Default")
      (node (ref "R6") (pin "2") (pinfunction "2_2") (pintype "passive"))
      (node (ref "U1") (pin "5") (pinfunction "QF_5") (pintype "output"))
    )
    (net (code "52") (name "Net-(U1-QG)") (class "Default")
      (node (ref "R7") (pin "2") (pinfunction "2_2") (pintype "passive"))
      (node (ref "U1") (pin "6") (pinfunction "QG_6") (pintype "output"))
    )
    (net (code "53") (name "Net-(U1-QH)") (class "Default")
      (node (ref "R8") (pin "2") (pinfunction "2_2") (pintype "passive"))
      (node (ref "U1") (pin "7") (pinfunction "QH_7") (pintype "output"))
    )
    (net (code "54") (name "Net-(U1-SQH)") (class "Default")
      (node (ref "U1") (pin "9") (pinfunction "SQH_9") (pintype "output"))
      (node (ref "U2") (pin "14") (pinfunction "A_14") (pintype "input"))
    )
    (net (code "55") (name "Net-(U2-QA)") (class "Default")
      (node (ref "R9") (pin "2") (pinfunction "2_2") (pintype "passive"))
      (node (ref "U2") (pin "15") (pinfunction "QA_15") (pintype "output"))
    )
    (net (code "56") (name "Net-(U2-QB)") (class "Default")
      (node (ref "R10") (pin "2") (pinfunction "2_2") (pintype "passive"))
      (node (ref "U2") (pin "1") (pinfunction "QB_1") (pintype "output"))
    )
    (net (code "57") (name "Net-(U2-QC)") (class "Default")
      (node (ref "R11") (pin "2") (pinfunction "2_2") (pintype "passive"))
      (node (ref "U2") (pin "2") (pinfunction "QC_2") (pintype "output"))
    )
    (net (code "58") (name "Net-(U2-QD)") (class "Default")
      (node (ref "R12") (pin "2") (pinfunction "2_2") (pintype "passive"))
      (node (ref "U2") (pin "3") (pinfunction "QD_3") (pintype "output"))
    )
    (net (code "59") (name "Net-(U2-QE)") (class "Default")
      (node (ref "R13") (pin "2") (pinfunction "2_2") (pintype "passive"))
      (node (ref "U2") (pin "4") (pinfunction "QE_4") (pintype "output"))
    )
    (net (code "60") (name "Net-(U2-QF)") (class "Default")
      (node (ref "R14") (pin "2") (pinfunction "2_2") (pintype "passive"))
      (node (ref "U2") (pin "5") (pinfunction "QF_5") (pintype "output"))
    )
    (net (code "61") (name "Net-(U2-QG)") (class "Default")
      (node (ref "R15") (pin "2") (pinfunction "2_2") (pintype "passive"))
      (node (ref "U2") (pin "6") (pinfunction "QG_6") (pintype "output"))
    )
    (net (code "62") (name "Net-(U2-QH)") (class "Default")
      (node (ref "R16") (pin "2") (pinfunction "2_2") (pintype "passive"))
      (node (ref "U2") (pin "7") (pinfunction "QH_7") (pintype "output"))
    )
    (net (code "63") (name "unconnected-(K1-Pad12)") (class "Default")
      (node (ref "K1") (pin "12") (pinfunction "12_12") (pintype "passive"))
    )
    (net (code "64") (name "unconnected-(SW1-Pad2)") (class "Default")
      (node (ref "SW1") (pin "2") (pinfunction "2_2") (pintype "passive"))
    )
    (net (code "65") (name "unconnected-(SW1-Pad4)") (class "Default")
      (node (ref "SW1") (pin "4") (pinfunction "4_4") (pintype "passive"))
    )
    (net (code "66") (name "unconnected-(SW2-Pad2)") (class "Default")
      (node (ref "SW2") (pin "2") (pinfunction "2_2") (pintype "passive"))
    )
    (net (code "67") (name "unconnected-(SW2-Pad4)") (class "Default")
      (node (ref "SW2") (pin "4") (pinfunction "4_4") (pintype "passive"))
    )
    (net (code "68") (name "unconnected-(U2-SQH-Pad9)") (class "Default")
      (node (ref "U2") (pin "9") (pinfunction "SQH_9") (pintype "output"))
    )
    (net (code "69") (name "unconnected-(U4-AREF-Pad21)") (class "Default")
      (node (ref "U4") (pin "21") (pinfunction "AREF_21") (pintype "power_in"))
    )
    (net (code "70") (name "unconnected-(U4-PB4_(MISO{slash}PCINT4)-Pad18)") (class "Default")
      (node (ref "U4") (pin "18") (pinfunction "PB4_(MISO/PCINT4)_18") (pintype "bidirectional"))
    )
    (net (code "71") (name "unconnected-(U4-PC0_(ADC0{slash}PCINT8)-Pad23)") (class "Default")
      (node (ref "U4") (pin "23") (pinfunction "PC0_(ADC0/PCINT8)_23") (pintype "bidirectional"))
    )
    (net (code "72") (name "unconnected-(U4-PC1_(ADC1{slash}PCINT9)-Pad24)") (class "Default")
      (node (ref "U4") (pin "24") (pinfunction "PC1_(ADC1/PCINT9)_24") (pintype "bidirectional"))
    )
    (net (code "73") (name "unconnected-(U4-PC2_(ADC2{slash}PCINT10)-Pad25)") (class "Default")
      (node (ref "U4") (pin "25") (pinfunction "PC2_(ADC2/PCINT10)_25") (pintype "bidirectional"))
    )
    (net (code "74") (name "unconnected-(U4-PC3_(ADC3{slash}PCINT11)-Pad26)") (class "Default")
      (node (ref "U4") (pin "26") (pinfunction "PC3_(ADC3/PCINT11)_26") (pintype "bidirectional"))
    )
  )
)
